# SC8701_EVM_RE1_0624_M6.net
KiCad netlist of a schematic drawn in Altium Designer
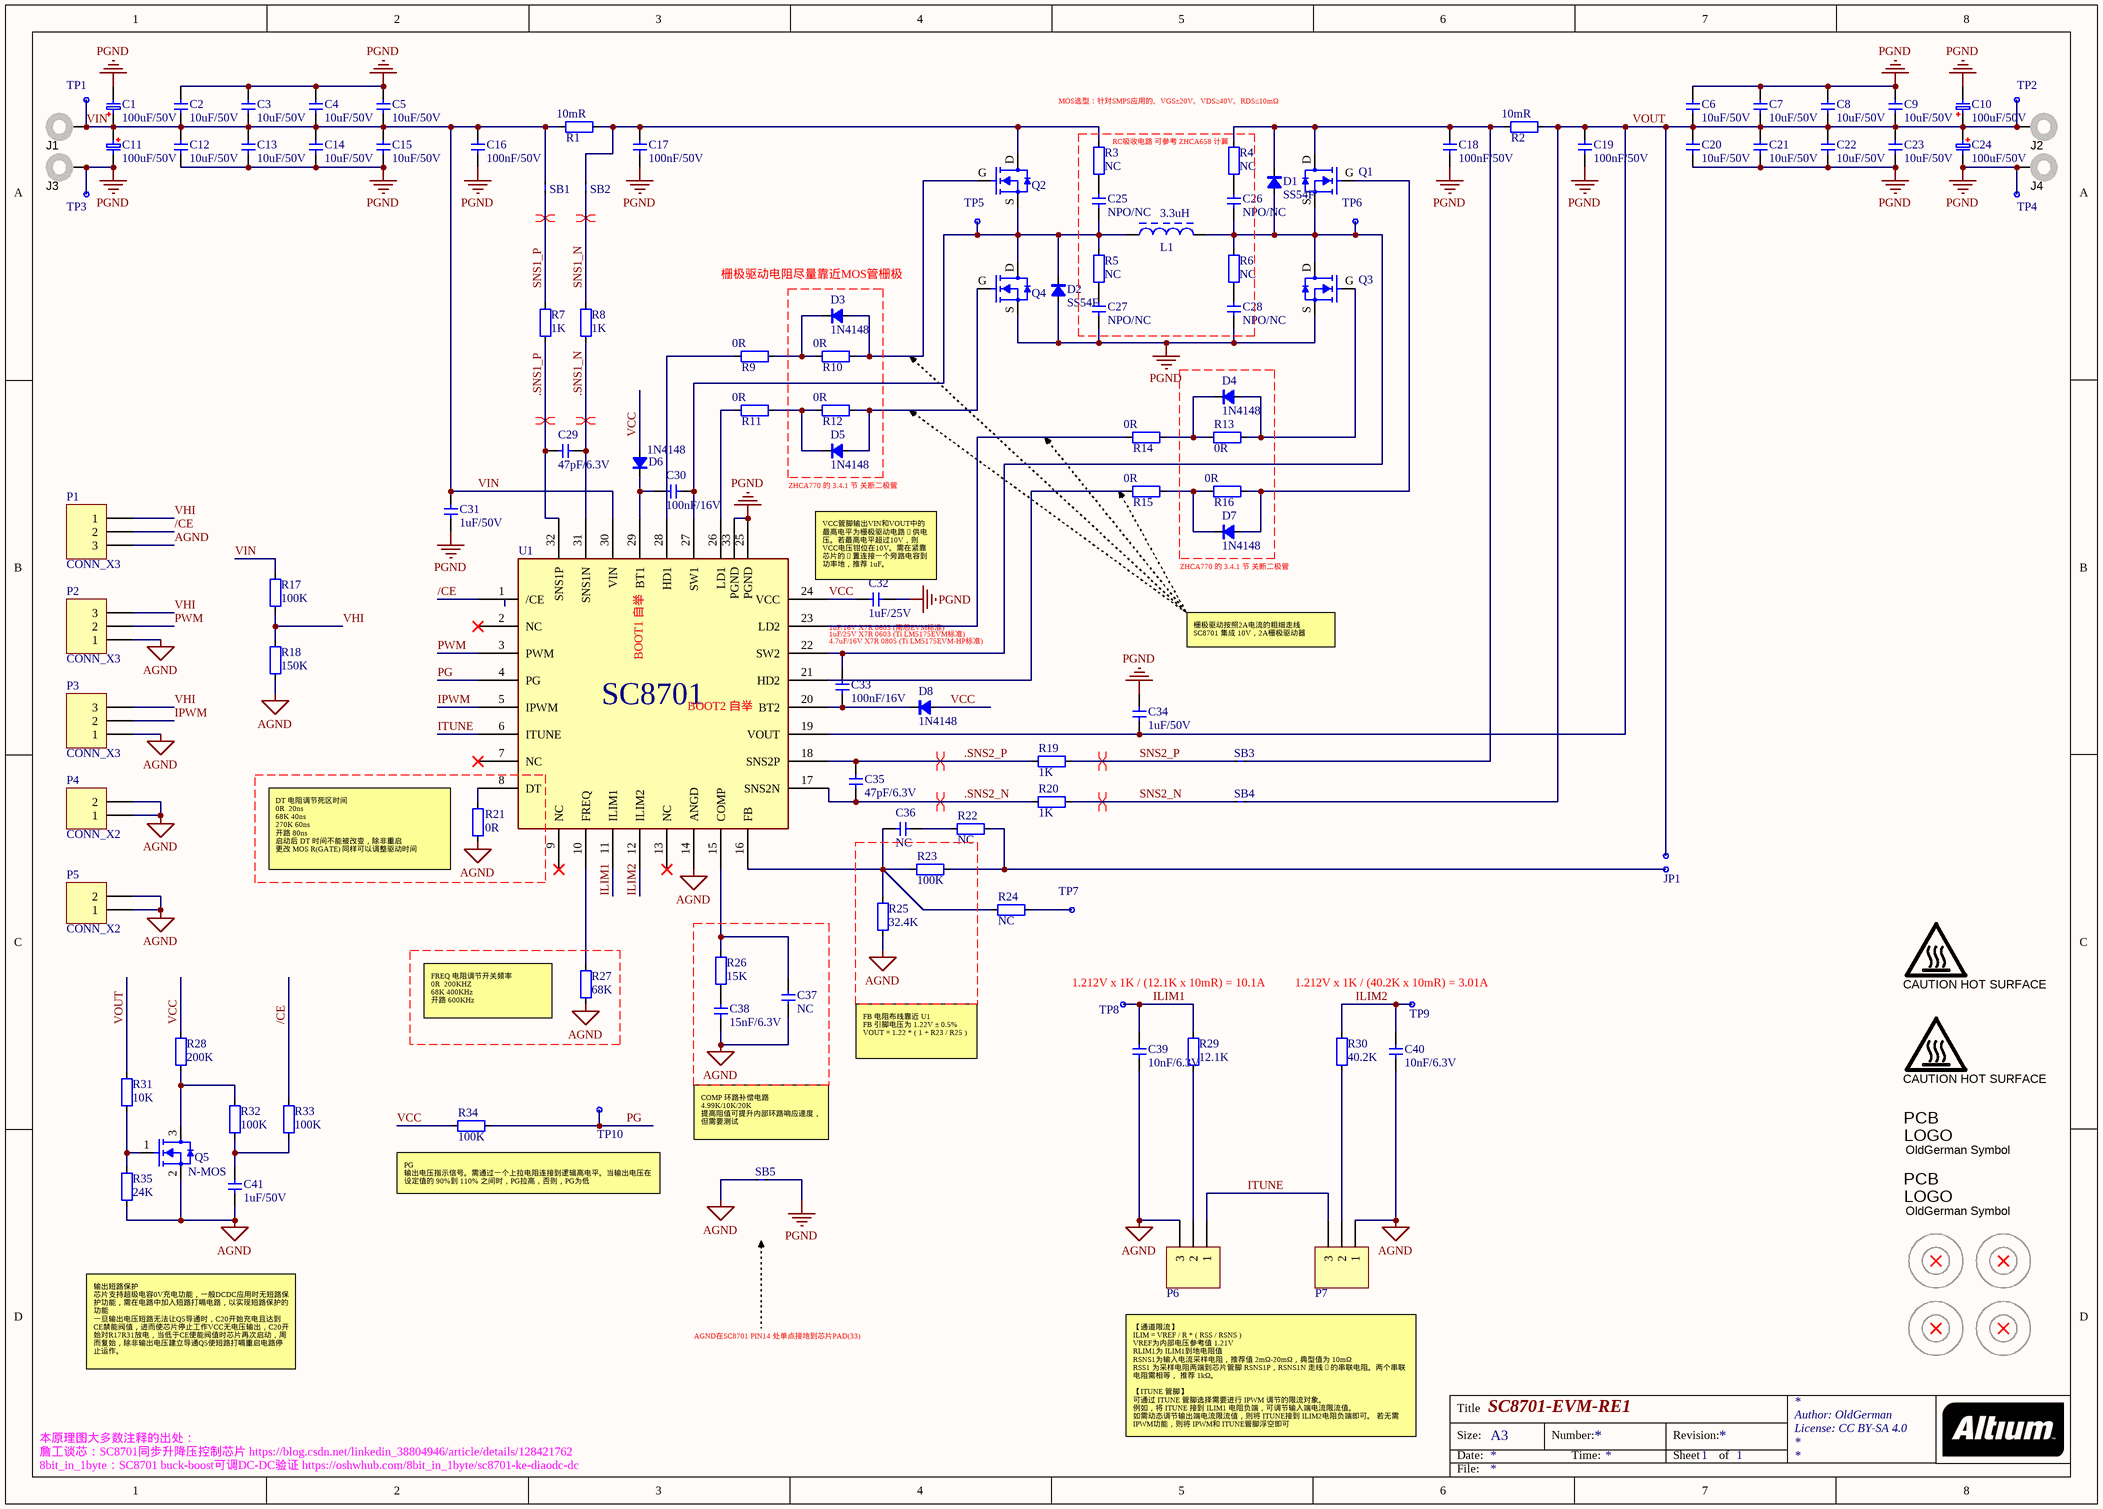
[diagram p0: SC8701_EVM_RE1_0624_M6.SchDoc]

(export (version "E")
  (design (tool "Eeschema 10.0.6"))
  (components
    (comp (ref "C1")
      (value "100uF/50V")
      (footprint "CAP OS-CON D=10.0 L=10.0 F10")
      (description "Capacitor")
      (libsource (lib "ODG_AD_Lib") (part "CAP_Polar_Aluminum"))
    )
    (comp (ref "C2")
      (value "10uF/50V")
      (footprint "C1210")
      (description "Capacitor")
      (libsource (lib "ODG_AD_Lib") (part "CAP"))
    )
    (comp (ref "C3")
      (value "10uF/50V")
      (footprint "C1210")
      (description "Capacitor")
      (libsource (lib "ODG_AD_Lib") (part "CAP"))
    )
    (comp (ref "C4")
      (value "10uF/50V")
      (footprint "C1210")
      (description "Capacitor")
      (libsource (lib "ODG_AD_Lib") (part "CAP"))
    )
    (comp (ref "C5")
      (value "10uF/50V")
      (footprint "C1210")
      (description "Capacitor")
      (libsource (lib "ODG_AD_Lib") (part "CAP"))
    )
    (comp (ref "C6")
      (value "10uF/50V")
      (footprint "C1210")
      (description "Capacitor")
      (libsource (lib "ODG_AD_Lib") (part "CAP"))
    )
    (comp (ref "C7")
      (value "10uF/50V")
      (footprint "C1210")
      (description "Capacitor")
      (libsource (lib "ODG_AD_Lib") (part "CAP"))
    )
    (comp (ref "C8")
      (value "10uF/50V")
      (footprint "C1210")
      (description "Capacitor")
      (libsource (lib "ODG_AD_Lib") (part "CAP"))
    )
    (comp (ref "C9")
      (value "10uF/50V")
      (footprint "C1210")
      (description "Capacitor")
      (libsource (lib "ODG_AD_Lib") (part "CAP"))
    )
    (comp (ref "C10")
      (value "100uF/50V")
      (footprint "CAP OS-CON D=10.0 L=10.0 F10")
      (description "Capacitor")
      (libsource (lib "ODG_AD_Lib") (part "CAP_Polar_Aluminum"))
    )
    (comp (ref "C11")
      (value "100uF/50V")
      (footprint "CAP OS-CON D=10.0 L=10.0 F10")
      (description "Capacitor")
      (libsource (lib "ODG_AD_Lib") (part "CAP_Polar_Aluminum"))
    )
    (comp (ref "C12")
      (value "10uF/50V")
      (footprint "C1210")
      (description "Capacitor")
      (libsource (lib "ODG_AD_Lib") (part "CAP"))
    )
    (comp (ref "C13")
      (value "10uF/50V")
      (footprint "C1210")
      (description "Capacitor")
      (libsource (lib "ODG_AD_Lib") (part "CAP"))
    )
    (comp (ref "C14")
      (value "10uF/50V")
      (footprint "C1210")
      (description "Capacitor")
      (libsource (lib "ODG_AD_Lib") (part "CAP"))
    )
    (comp (ref "C15")
      (value "10uF/50V")
      (footprint "C1210")
      (description "Capacitor")
      (libsource (lib "ODG_AD_Lib") (part "CAP"))
    )
    (comp (ref "C16")
      (value "100nF/50V")
      (footprint "C0603")
      (description "Capacitor")
      (libsource (lib "ODG_AD_Lib") (part "CAP"))
    )
    (comp (ref "C17")
      (value "100nF/50V")
      (footprint "C0603")
      (description "Capacitor")
      (libsource (lib "ODG_AD_Lib") (part "CAP"))
    )
    (comp (ref "C18")
      (value "100nF/50V")
      (footprint "C0603")
      (description "Capacitor")
      (libsource (lib "ODG_AD_Lib") (part "CAP"))
    )
    (comp (ref "C19")
      (value "100nF/50V")
      (footprint "C0603")
      (description "Capacitor")
      (libsource (lib "ODG_AD_Lib") (part "CAP"))
    )
    (comp (ref "C20")
      (value "10uF/50V")
      (footprint "C1210")
      (description "Capacitor")
      (libsource (lib "ODG_AD_Lib") (part "CAP"))
    )
    (comp (ref "C21")
      (value "10uF/50V")
      (footprint "C1210")
      (description "Capacitor")
      (libsource (lib "ODG_AD_Lib") (part "CAP"))
    )
    (comp (ref "C22")
      (value "10uF/50V")
      (footprint "C1210")
      (description "Capacitor")
      (libsource (lib "ODG_AD_Lib") (part "CAP"))
    )
    (comp (ref "C23")
      (value "10uF/50V")
      (footprint "C1210")
      (description "Capacitor")
      (libsource (lib "ODG_AD_Lib") (part "CAP"))
    )
    (comp (ref "C24")
      (value "100uF/50V")
      (footprint "CAP OS-CON D=10.0 L=10.0 F10")
      (description "Capacitor")
      (libsource (lib "ODG_AD_Lib") (part "CAP_Polar_Aluminum"))
    )
    (comp (ref "C25")
      (value "NPO/NC")
      (footprint "C0805")
      (description "Capacitor")
      (libsource (lib "ODG_AD_Lib") (part "CAP"))
    )
    (comp (ref "C26")
      (value "NPO/NC")
      (footprint "C0805")
      (description "Capacitor")
      (libsource (lib "ODG_AD_Lib") (part "CAP"))
    )
    (comp (ref "C27")
      (value "NPO/NC")
      (footprint "C0805")
      (description "Capacitor")
      (libsource (lib "ODG_AD_Lib") (part "CAP"))
    )
    (comp (ref "C28")
      (value "NPO/NC")
      (footprint "C0805")
      (description "Capacitor")
      (libsource (lib "ODG_AD_Lib") (part "CAP"))
    )
    (comp (ref "C29")
      (value "47pF/6.3V")
      (footprint "C0603")
      (description "Capacitor")
      (libsource (lib "ODG_AD_Lib") (part "CAP"))
    )
    (comp (ref "C30")
      (value "100nF/16V")
      (footprint "C0603")
      (description "Capacitor")
      (libsource (lib "ODG_AD_Lib") (part "CAP"))
    )
    (comp (ref "C31")
      (value "1uF/50V")
      (footprint "C0603")
      (description "Capacitor")
      (libsource (lib "ODG_AD_Lib") (part "CAP"))
    )
    (comp (ref "C32")
      (value "1uF/25V")
      (footprint "C0805")
      (description "Capacitor")
      (libsource (lib "ODG_AD_Lib") (part "CAP"))
    )
    (comp (ref "C33")
      (value "100nF/16V")
      (footprint "C0603")
      (description "Capacitor")
      (libsource (lib "ODG_AD_Lib") (part "CAP"))
    )
    (comp (ref "C34")
      (value "1uF/50V")
      (footprint "C0603")
      (description "Capacitor")
      (libsource (lib "ODG_AD_Lib") (part "CAP"))
    )
    (comp (ref "C35")
      (value "47pF/6.3V")
      (footprint "C0603")
      (description "Capacitor")
      (libsource (lib "ODG_AD_Lib") (part "CAP"))
    )
    (comp (ref "C36")
      (value "NC")
      (footprint "C0603")
      (description "Capacitor")
      (libsource (lib "ODG_AD_Lib") (part "CAP"))
    )
    (comp (ref "C37")
      (value "NC")
      (footprint "C0603")
      (description "Capacitor")
      (libsource (lib "ODG_AD_Lib") (part "CAP"))
    )
    (comp (ref "C38")
      (value "15nF/6.3V")
      (footprint "C0603")
      (description "Capacitor")
      (libsource (lib "ODG_AD_Lib") (part "CAP"))
    )
    (comp (ref "C39")
      (value "10nF/6.3V")
      (footprint "C0603")
      (description "Capacitor")
      (libsource (lib "ODG_AD_Lib") (part "CAP"))
    )
    (comp (ref "C40")
      (value "10nF/6.3V")
      (footprint "C0603")
      (description "Capacitor")
      (libsource (lib "ODG_AD_Lib") (part "CAP"))
    )
    (comp (ref "C41")
      (value "1uF/50V")
      (footprint "C0603")
      (description "Capacitor")
      (libsource (lib "ODG_AD_Lib") (part "CAP"))
    )
    (comp (ref "D1")
      (value "SS54F")
      (footprint "SMAF")
      (description "二极管")
      (libsource (lib "") (part "DIODE_2"))
    )
    (comp (ref "D2")
      (value "SS54F")
      (footprint "SMAF")
      (description "二极管")
      (libsource (lib "") (part "DIODE_2"))
    )
    (comp (ref "D3")
      (value "1N4148")
      (footprint "SOD-323")
      (description "二极管")
      (libsource (lib "") (part "DIODE_1"))
    )
    (comp (ref "D4")
      (value "1N4148")
      (footprint "SOD-323")
      (description "二极管")
      (libsource (lib "") (part "DIODE_1"))
    )
    (comp (ref "D5")
      (value "1N4148")
      (footprint "SOD-323")
      (description "二极管")
      (libsource (lib "") (part "DIODE_1"))
    )
    (comp (ref "D6")
      (value "1N4148")
      (footprint "SOD-323")
      (description "二极管")
      (libsource (lib "ODG_AD_Lib") (part "DIODE"))
    )
    (comp (ref "D7")
      (value "1N4148")
      (footprint "SOD-323")
      (description "二极管")
      (libsource (lib "") (part "DIODE_1"))
    )
    (comp (ref "D8")
      (value "1N4148")
      (footprint "SOD-323")
      (description "二极管")
      (libsource (lib "") (part "DIODE_1"))
    )
    (comp (ref "H1") (value "HOLE") (footprint "M3.2 D=8") (libsource (lib "ODG_AD_Lib") (part "HOLE")))
    (comp (ref "H2") (value "HOLE") (footprint "M3.2 D=8") (libsource (lib "ODG_AD_Lib") (part "HOLE")))
    (comp (ref "H3") (value "HOLE") (footprint "M3.2 D=8") (libsource (lib "ODG_AD_Lib") (part "HOLE")))
    (comp (ref "H4") (value "HOLE") (footprint "M3.2 D=8") (libsource (lib "ODG_AD_Lib") (part "HOLE")))
    (comp (ref "J1")
      (value "U6047")
      (footprint "JACK_BANANA_4MM_M6_GE")
      (description "Banana Jack")
      (fields
        (field (name "PARTNUMBER") "575-8")
        (field (name "MANUFACTURER") "Keystone")
        (field (name "PUBLISHER") "Texas Instruments")
      )
      (libsource (lib "ODG_AD_Lib") (part "JACK_BANANA"))
    )
    (comp (ref "J2")
      (value "U6047")
      (footprint "JACK_BANANA_4MM_M6_GE")
      (description "Banana Jack")
      (fields
        (field (name "PARTNUMBER") "575-8")
        (field (name "MANUFACTURER") "Keystone")
        (field (name "PUBLISHER") "Texas Instruments")
      )
      (libsource (lib "ODG_AD_Lib") (part "JACK_BANANA"))
    )
    (comp (ref "J3")
      (value "U6047")
      (footprint "JACK_BANANA_4MM_M6_GE")
      (description "Banana Jack")
      (fields
        (field (name "PARTNUMBER") "575-8")
        (field (name "MANUFACTURER") "Keystone")
        (field (name "PUBLISHER") "Texas Instruments")
      )
      (libsource (lib "ODG_AD_Lib") (part "JACK_BANANA"))
    )
    (comp (ref "J4")
      (value "U6047")
      (footprint "JACK_BANANA_4MM_M6_GE")
      (description "Banana Jack")
      (fields
        (field (name "PARTNUMBER") "575-8")
        (field (name "MANUFACTURER") "Keystone")
        (field (name "PUBLISHER") "Texas Instruments")
      )
      (libsource (lib "ODG_AD_Lib") (part "JACK_BANANA"))
    )
    (comp (ref "JP1")
      (value "CONN_X2_DOT")
      (footprint "2.54mm_Male_x2")
      (libsource (lib "ODG_AD_Lib") (part "CONN_X2_DOT"))
    )
    (comp (ref "L1")
      (value "3.3uH")
      (footprint "INDUCTOR 1350 12.6X13.5X5.0mm")
      (description "135 功率电感 额定电流15A")
      (libsource (lib "ODG_AD_Lib") (part "Inductor_power"))
    )
    (comp (ref "LOGO1")
      (value "CAUTION HOT SURFACE")
      (footprint "IEC_HotSurface_Small")
      (description "IEC 61010-1 Hot Surface Warning")
      (fields (field (name "SYMBOLCREATOR") "a0412235") (field (name "PUBLISHER") "Texas Instruments"))
      (libsource (lib "ODG_AD_Lib") (part "IEC_HotSurface"))
    )
    (comp (ref "LOGO2")
      (value "CAUTION HOT SURFACE")
      (footprint "IEC_HotSurface_Small")
      (description "IEC 61010-1 Hot Surface Warning")
      (fields (field (name "SYMBOLCREATOR") "a0412235") (field (name "PUBLISHER") "Texas Instruments"))
      (libsource (lib "ODG_AD_Lib") (part "IEC_HotSurface"))
    )
    (comp (ref "Logo3")
      (value "OldGerman Symbol")
      (footprint "ODG_LOGO")
      (fields (field (name "SYMBOLCREATOR") "a0412235") (field (name "PUBLISHER") "Texas Instruments"))
      (libsource (lib "ODG_AD_Lib") (part "OldGeman"))
    )
    (comp (ref "Logo4")
      (value "OldGerman Symbol")
      (footprint "ODG_LOGO")
      (fields (field (name "SYMBOLCREATOR") "a0412235") (field (name "PUBLISHER") "Texas Instruments"))
      (libsource (lib "ODG_AD_Lib") (part "OldGeman"))
    )
    (comp (ref "P1") (value "CONN_X3") (footprint "2.54mm_Male_x3") (libsource (lib "") (part "CONN_X3_1")))
    (comp (ref "P2")
      (value "CONN_X3")
      (footprint "2.54mm_Male_x3")
      (libsource (lib "ODG_AD_Lib") (part "CONN_X3"))
    )
    (comp (ref "P3")
      (value "CONN_X3")
      (footprint "2.54mm_Male_x3")
      (libsource (lib "ODG_AD_Lib") (part "CONN_X3"))
    )
    (comp (ref "P4")
      (value "CONN_X2")
      (footprint "2.54mm_Male_x2")
      (libsource (lib "ODG_AD_Lib") (part "CONN_X2"))
    )
    (comp (ref "P5")
      (value "CONN_X2")
      (footprint "2.54mm_Male_x2")
      (libsource (lib "ODG_AD_Lib") (part "CONN_X2"))
    )
    (comp (ref "P6") (value "CONN_X3") (footprint "2.54mm_Male_x3") (libsource (lib "") (part "CONN_X3_1")))
    (comp (ref "P7") (value "CONN_X3") (footprint "2.54mm_Male_x3") (libsource (lib "") (part "CONN_X3_1")))
    (comp (ref "Q1")
      (value "N-MOS_GDS")
      (footprint "SO8FL ROUND")
      (libsource (lib "ODG_AD_Lib") (part "N-MOS_GDS"))
    )
    (comp (ref "Q2")
      (value "N-MOS_GDS")
      (footprint "SO8FL ROUND")
      (libsource (lib "ODG_AD_Lib") (part "N-MOS_GDS"))
    )
    (comp (ref "Q3")
      (value "N-MOS_GDS")
      (footprint "SO8FL ROUND")
      (libsource (lib "ODG_AD_Lib") (part "N-MOS_GDS"))
    )
    (comp (ref "Q4")
      (value "N-MOS_GDS")
      (footprint "SO8FL ROUND")
      (libsource (lib "ODG_AD_Lib") (part "N-MOS_GDS"))
    )
    (comp (ref "Q5")
      (value "N-MOS")
      (footprint "INFINEON SOT-23-3")
      (libsource (lib "ODG_AD_Lib") (part "N-MOS_123"))
    )
    (comp (ref "R1")
      (value "10mR")
      (footprint "R1206")
      (description "IEC Standard")
      (libsource (lib "ODG_AD_Lib") (part "RES"))
    )
    (comp (ref "R2")
      (value "10mR")
      (footprint "R1206")
      (description "IEC Standard")
      (libsource (lib "ODG_AD_Lib") (part "RES"))
    )
    (comp (ref "R3")
      (value "NC")
      (footprint "R0805")
      (description "IEC Standard")
      (libsource (lib "") (part "RES_1"))
    )
    (comp (ref "R4")
      (value "NC")
      (footprint "R0805")
      (description "IEC Standard")
      (libsource (lib "") (part "RES_1"))
    )
    (comp (ref "R5")
      (value "NC")
      (footprint "R0805")
      (description "IEC Standard")
      (libsource (lib "") (part "RES_1"))
    )
    (comp (ref "R6")
      (value "NC")
      (footprint "R0805")
      (description "IEC Standard")
      (libsource (lib "") (part "RES_1"))
    )
    (comp (ref "R7")
      (value "1K")
      (footprint "R0603")
      (description "IEC Standard")
      (libsource (lib "") (part "RES_1"))
    )
    (comp (ref "R8")
      (value "1K")
      (footprint "R0603")
      (description "IEC Standard")
      (libsource (lib "") (part "RES_1"))
    )
    (comp (ref "R9")
      (value "0R")
      (footprint "R0603")
      (description "IEC Standard")
      (libsource (lib "ODG_AD_Lib") (part "RES"))
    )
    (comp (ref "R10")
      (value "0R")
      (footprint "R0603")
      (description "IEC Standard")
      (libsource (lib "ODG_AD_Lib") (part "RES"))
    )
    (comp (ref "R11")
      (value "0R")
      (footprint "R0603")
      (description "IEC Standard")
      (libsource (lib "ODG_AD_Lib") (part "RES"))
    )
    (comp (ref "R12")
      (value "0R")
      (footprint "R0603")
      (description "IEC Standard")
      (libsource (lib "ODG_AD_Lib") (part "RES"))
    )
    (comp (ref "R13")
      (value "0R")
      (footprint "R0603")
      (description "IEC Standard")
      (libsource (lib "ODG_AD_Lib") (part "RES"))
    )
    (comp (ref "R14")
      (value "0R")
      (footprint "R0603")
      (description "IEC Standard")
      (libsource (lib "ODG_AD_Lib") (part "RES"))
    )
    (comp (ref "R15")
      (value "0R")
      (footprint "R0603")
      (description "IEC Standard")
      (libsource (lib "ODG_AD_Lib") (part "RES"))
    )
    (comp (ref "R16")
      (value "0R")
      (footprint "R0603")
      (description "IEC Standard")
      (libsource (lib "ODG_AD_Lib") (part "RES"))
    )
    (comp (ref "R17")
      (value "100K")
      (footprint "R0603")
      (description "IEC Standard")
      (libsource (lib "") (part "RES_1"))
    )
    (comp (ref "R18")
      (value "150K")
      (footprint "R0603")
      (description "IEC Standard")
      (libsource (lib "") (part "RES_1"))
    )
    (comp (ref "R19")
      (value "1K")
      (footprint "R0603")
      (description "IEC Standard")
      (libsource (lib "") (part "RES_2"))
    )
    (comp (ref "R20")
      (value "1K")
      (footprint "R0603")
      (description "IEC Standard")
      (libsource (lib "") (part "RES_2"))
    )
    (comp (ref "R21")
      (value "0R")
      (footprint "R0603")
      (description "IEC Standard")
      (libsource (lib "") (part "RES_1"))
    )
    (comp (ref "R22")
      (value "NC")
      (footprint "R0603")
      (description "IEC Standard")
      (libsource (lib "") (part "RES_2"))
    )
    (comp (ref "R23")
      (value "100K")
      (footprint "R0603")
      (description "IEC Standard")
      (libsource (lib "ODG_AD_Lib") (part "RES"))
    )
    (comp (ref "R24")
      (value "NC")
      (footprint "R0603")
      (description "IEC Standard")
      (libsource (lib "") (part "RES_2"))
    )
    (comp (ref "R25")
      (value "32.4K")
      (footprint "R0603")
      (description "IEC Standard")
      (libsource (lib "") (part "RES_1"))
    )
    (comp (ref "R26")
      (value "15K")
      (footprint "R0603")
      (description "IEC Standard")
      (libsource (lib "") (part "RES_1"))
    )
    (comp (ref "R27")
      (value "68K")
      (footprint "R0603")
      (description "IEC Standard")
      (libsource (lib "") (part "RES_1"))
    )
    (comp (ref "R28")
      (value "200K")
      (footprint "R0603")
      (description "IEC Standard")
      (libsource (lib "") (part "RES_1"))
    )
    (comp (ref "R29")
      (value "12.1K")
      (footprint "R0603")
      (description "IEC Standard")
      (libsource (lib "") (part "RES_1"))
    )
    (comp (ref "R30")
      (value "40.2K")
      (footprint "R0603")
      (description "IEC Standard")
      (libsource (lib "") (part "RES_1"))
    )
    (comp (ref "R31")
      (value "10K")
      (footprint "R0603")
      (description "IEC Standard")
      (libsource (lib "") (part "RES_1"))
    )
    (comp (ref "R32")
      (value "100K")
      (footprint "R0603")
      (description "IEC Standard")
      (libsource (lib "") (part "RES_1"))
    )
    (comp (ref "R33")
      (value "100K")
      (footprint "R0603")
      (description "IEC Standard")
      (libsource (lib "") (part "RES_1"))
    )
    (comp (ref "R34")
      (value "100K")
      (footprint "R0603")
      (description "IEC Standard")
      (libsource (lib "ODG_AD_Lib") (part "RES"))
    )
    (comp (ref "R35")
      (value "24K")
      (footprint "R0603")
      (description "IEC Standard")
      (libsource (lib "") (part "RES_1"))
    )
    (comp (ref "SB1")
      (value "NetTie_200um")
      (footprint "NetTie_200um")
      (description "Net Tie")
      (fields (field (name "PART NUMBER") "NetTie 0.2mm") (field (name "PUBLISHER") "Nordic Semiconductor"))
      (libsource (lib "pca63100") (part "NetTie 0.2mm"))
    )
    (comp (ref "SB2")
      (value "NetTie_200um")
      (footprint "NetTie_200um")
      (description "Net Tie")
      (fields (field (name "PART NUMBER") "NetTie 0.2mm") (field (name "PUBLISHER") "Nordic Semiconductor"))
      (libsource (lib "pca63100") (part "NetTie 0.2mm"))
    )
    (comp (ref "SB3")
      (value "NetTie_200um")
      (footprint "NetTie_200um")
      (description "Net Tie")
      (fields (field (name "PART NUMBER") "NetTie 0.2mm") (field (name "PUBLISHER") "Nordic Semiconductor"))
      (libsource (lib "pca63100") (part "NetTie 0.2mm"))
    )
    (comp (ref "SB4")
      (value "NetTie_200um")
      (footprint "NetTie_200um")
      (description "Net Tie")
      (fields (field (name "PART NUMBER") "NetTie 0.2mm") (field (name "PUBLISHER") "Nordic Semiconductor"))
      (libsource (lib "pca63100") (part "NetTie 0.2mm"))
    )
    (comp (ref "SB5")
      (value "NetTie_200um")
      (footprint "NetTie_200um")
      (description "Net Tie")
      (fields (field (name "PART NUMBER") "NetTie 0.2mm") (field (name "PUBLISHER") "Nordic Semiconductor"))
      (libsource (lib "pca63100") (part "NetTie 0.2mm"))
    )
    (comp (ref "TP1")
      (value "CONN_X1_DOT")
      (footprint "2.54mm_Male_x1")
      (libsource (lib "ODG_AD_Lib") (part "CONN_X1_DOT"))
    )
    (comp (ref "TP2")
      (value "CONN_X1_DOT")
      (footprint "2.54mm_Male_x1")
      (libsource (lib "ODG_AD_Lib") (part "CONN_X1_DOT"))
    )
    (comp (ref "TP3")
      (value "CONN_X1_DOT")
      (footprint "2.54mm_Male_x1")
      (libsource (lib "ODG_AD_Lib") (part "CONN_X1_DOT"))
    )
    (comp (ref "TP4")
      (value "CONN_X1_DOT")
      (footprint "2.54mm_Male_x1")
      (libsource (lib "ODG_AD_Lib") (part "CONN_X1_DOT"))
    )
    (comp (ref "TP5")
      (value "CONN_X1_DOT")
      (footprint "2.54mm_Male_x1")
      (libsource (lib "ODG_AD_Lib") (part "CONN_X1_DOT"))
    )
    (comp (ref "TP6")
      (value "CONN_X1_DOT")
      (footprint "2.54mm_Male_x1")
      (libsource (lib "ODG_AD_Lib") (part "CONN_X1_DOT"))
    )
    (comp (ref "TP7")
      (value "CONN_X1_DOT")
      (footprint "2.54mm_Male_x1")
      (libsource (lib "ODG_AD_Lib") (part "CONN_X1_DOT"))
    )
    (comp (ref "TP8")
      (value "CONN_X1_DOT")
      (footprint "2.54mm_Male_x1")
      (libsource (lib "ODG_AD_Lib") (part "CONN_X1_DOT"))
    )
    (comp (ref "TP9")
      (value "CONN_X1_DOT")
      (footprint "2.54mm_Male_x1")
      (libsource (lib "ODG_AD_Lib") (part "CONN_X1_DOT"))
    )
    (comp (ref "TP10")
      (value "CONN_X1_DOT")
      (footprint "2.54mm_Male_x1")
      (libsource (lib "ODG_AD_Lib") (part "CONN_X1_DOT"))
    )
    (comp (ref "U1")
      (value "SC8701 (A)")
      (footprint "TQFN-32 4X4MM 0.4 VIA")
      (description "高效率, 同步, 4 管升降压控制器")
      (libsource (lib "ODG_AD_Lib") (part "SC8701 (A)"))
    )
  )
  (nets
    (net (code "1") (name "/.SNS1_N") (class "Default")
      (node (ref "C29") (pin "2") (pinfunction "2_2") (pintype "passive"))
      (node (ref "R8") (pin "1") (pinfunction "1_1") (pintype "passive"))
      (node (ref "U1") (pin "31") (pinfunction "SNS1N_31") (pintype "passive"))
    )
    (net (code "2") (name "/.SNS1_P") (class "Default")
      (node (ref "C29") (pin "1") (pinfunction "1_1") (pintype "passive"))
      (node (ref "R7") (pin "1") (pinfunction "1_1") (pintype "passive"))
      (node (ref "U1") (pin "32") (pinfunction "SNS1P_32") (pintype "passive"))
    )
    (net (code "3") (name "/.SNS2_N") (class "Default")
      (node (ref "C35") (pin "2") (pinfunction "2_2") (pintype "passive"))
      (node (ref "R20") (pin "2") (pinfunction "2_2") (pintype "passive"))
      (node (ref "U1") (pin "17") (pinfunction "SNS2N_17") (pintype "passive"))
    )
    (net (code "4") (name "/.SNS2_P") (class "Default")
      (node (ref "C35") (pin "1") (pinfunction "1_1") (pintype "passive"))
      (node (ref "R19") (pin "2") (pinfunction "2_2") (pintype "passive"))
      (node (ref "U1") (pin "18") (pinfunction "SNS2P_18") (pintype "passive"))
    )
    (net (code "5") (name "/ILIM1") (class "Default")
      (node (ref "C39") (pin "2") (pinfunction "2_2") (pintype "passive"))
      (node (ref "R29") (pin "2") (pinfunction "2_2") (pintype "passive"))
      (node (ref "TP8") (pin "1") (pinfunction "1_1") (pintype "passive"))
      (node (ref "U1") (pin "11") (pinfunction "ILIM1_11") (pintype "passive"))
    )
    (net (code "6") (name "/ILIM2") (class "Default")
      (node (ref "C40") (pin "2") (pinfunction "2_2") (pintype "passive"))
      (node (ref "R30") (pin "2") (pinfunction "2_2") (pintype "passive"))
      (node (ref "TP9") (pin "1") (pinfunction "1_1") (pintype "passive"))
      (node (ref "U1") (pin "12") (pinfunction "ILIM2_12") (pintype "passive"))
    )
    (net (code "7") (name "/IPWM") (class "Default")
      (node (ref "P3") (pin "2") (pinfunction "2_2") (pintype "passive"))
      (node (ref "U1") (pin "5") (pinfunction "IPWM_5") (pintype "passive"))
    )
    (net (code "8") (name "/ITUNE") (class "Default")
      (node (ref "P6") (pin "1") (pinfunction "1_1") (pintype "passive"))
      (node (ref "P7") (pin "3") (pinfunction "3_3") (pintype "passive"))
      (node (ref "U1") (pin "6") (pinfunction "ITUNE_6") (pintype "passive"))
    )
    (net (code "9") (name "/PG") (class "Default")
      (node (ref "R34") (pin "2") (pinfunction "2_2") (pintype "passive"))
      (node (ref "TP10") (pin "1") (pinfunction "1_1") (pintype "passive"))
      (node (ref "U1") (pin "4") (pinfunction "PG_4") (pintype "passive"))
    )
    (net (code "10") (name "/PWM") (class "Default")
      (node (ref "P2") (pin "2") (pinfunction "2_2") (pintype "passive"))
      (node (ref "U1") (pin "3") (pinfunction "PWM_3") (pintype "passive"))
    )
    (net (code "11") (name "/SNS1_N") (class "Default")
      (node (ref "R8") (pin "2") (pinfunction "2_2") (pintype "passive"))
      (node (ref "SB2") (pin "1") (pinfunction "1_1") (pintype "passive"))
    )
    (net (code "12") (name "/SNS1_P") (class "Default")
      (node (ref "R7") (pin "2") (pinfunction "2_2") (pintype "passive"))
      (node (ref "SB1") (pin "1") (pinfunction "1_1") (pintype "passive"))
    )
    (net (code "13") (name "/SNS2_N") (class "Default")
      (node (ref "R20") (pin "1") (pinfunction "1_1") (pintype "passive"))
      (node (ref "SB4") (pin "1") (pinfunction "1_1") (pintype "passive"))
    )
    (net (code "14") (name "/SNS2_P") (class "Default")
      (node (ref "R19") (pin "1") (pinfunction "1_1") (pintype "passive"))
      (node (ref "SB3") (pin "1") (pinfunction "1_1") (pintype "passive"))
    )
    (net (code "15") (name "/VCC") (class "Default")
      (node (ref "C32") (pin "1") (pinfunction "1_1") (pintype "passive"))
      (node (ref "D6") (pin "1") (pinfunction "A_1") (pintype "passive"))
      (node (ref "D8") (pin "1") (pinfunction "A_1") (pintype "passive"))
      (node (ref "R28") (pin "2") (pinfunction "2_2") (pintype "passive"))
      (node (ref "R34") (pin "1") (pinfunction "1_1") (pintype "passive"))
      (node (ref "U1") (pin "24") (pinfunction "VCC_24") (pintype "passive"))
    )
    (net (code "16") (name "/VHI") (class "Default")
      (node (ref "P1") (pin "1") (pinfunction "1_1") (pintype "passive"))
      (node (ref "P2") (pin "3") (pinfunction "3_3") (pintype "passive"))
      (node (ref "P3") (pin "3") (pinfunction "3_3") (pintype "passive"))
      (node (ref "R17") (pin "1") (pinfunction "1_1") (pintype "passive"))
      (node (ref "R18") (pin "2") (pinfunction "2_2") (pintype "passive"))
    )
    (net (code "17") (name "/VIN") (class "Default")
      (node (ref "C1") (pin "1") (pinfunction "1_1") (pintype "passive"))
      (node (ref "C11") (pin "1") (pinfunction "1_1") (pintype "passive"))
      (node (ref "C12") (pin "2") (pinfunction "2_2") (pintype "passive"))
      (node (ref "C13") (pin "2") (pinfunction "2_2") (pintype "passive"))
      (node (ref "C14") (pin "2") (pinfunction "2_2") (pintype "passive"))
      (node (ref "C15") (pin "2") (pinfunction "2_2") (pintype "passive"))
      (node (ref "C16") (pin "2") (pinfunction "2_2") (pintype "passive"))
      (node (ref "C2") (pin "2") (pinfunction "2_2") (pintype "passive"))
      (node (ref "C3") (pin "2") (pinfunction "2_2") (pintype "passive"))
      (node (ref "C31") (pin "1") (pinfunction "1_1") (pintype "passive"))
      (node (ref "C4") (pin "2") (pinfunction "2_2") (pintype "passive"))
      (node (ref "C5") (pin "2") (pinfunction "2_2") (pintype "passive"))
      (node (ref "J1") (pin "1") (pinfunction "1_1") (pintype "passive"))
      (node (ref "R1") (pin "1") (pinfunction "1_1") (pintype "passive"))
      (node (ref "R17") (pin "2") (pinfunction "2_2") (pintype "passive"))
      (node (ref "SB1") (pin "2") (pinfunction "2_2") (pintype "passive"))
      (node (ref "TP1") (pin "1") (pinfunction "1_1") (pintype "passive"))
      (node (ref "U1") (pin "30") (pinfunction "VIN_30") (pintype "passive"))
    )
    (net (code "18") (name "/VOUT") (class "Default")
      (node (ref "C10") (pin "1") (pinfunction "1_1") (pintype "passive"))
      (node (ref "C19") (pin "2") (pinfunction "2_2") (pintype "passive"))
      (node (ref "C20") (pin "2") (pinfunction "2_2") (pintype "passive"))
      (node (ref "C21") (pin "2") (pinfunction "2_2") (pintype "passive"))
      (node (ref "C22") (pin "2") (pinfunction "2_2") (pintype "passive"))
      (node (ref "C23") (pin "2") (pinfunction "2_2") (pintype "passive"))
      (node (ref "C24") (pin "1") (pinfunction "1_1") (pintype "passive"))
      (node (ref "C34") (pin "1") (pinfunction "1_1") (pintype "passive"))
      (node (ref "C6") (pin "2") (pinfunction "2_2") (pintype "passive"))
      (node (ref "C7") (pin "2") (pinfunction "2_2") (pintype "passive"))
      (node (ref "C8") (pin "2") (pinfunction "2_2") (pintype "passive"))
      (node (ref "C9") (pin "2") (pinfunction "2_2") (pintype "passive"))
      (node (ref "J2") (pin "1") (pinfunction "1_1") (pintype "passive"))
      (node (ref "JP1") (pin "1") (pinfunction "1_1") (pintype "passive"))
      (node (ref "R2") (pin "2") (pinfunction "2_2") (pintype "passive"))
      (node (ref "R31") (pin "2") (pinfunction "2_2") (pintype "passive"))
      (node (ref "SB4") (pin "2") (pinfunction "2_2") (pintype "passive"))
      (node (ref "TP2") (pin "1") (pinfunction "1_1") (pintype "passive"))
      (node (ref "U1") (pin "19") (pinfunction "VOUT_19") (pintype "passive"))
    )
    (net (code "19") (name "/{slash}CE") (class "Default")
      (node (ref "P1") (pin "2") (pinfunction "2_2") (pintype "passive"))
      (node (ref "R33") (pin "2") (pinfunction "2_2") (pintype "passive"))
      (node (ref "U1") (pin "1") (pinfunction "/CE_1") (pintype "passive"))
    )
    (net (code "20") (name "AGND") (class "Default")
      (node (ref "C37") (pin "1") (pinfunction "1_1") (pintype "passive"))
      (node (ref "C38") (pin "1") (pinfunction "1_1") (pintype "passive"))
      (node (ref "C39") (pin "1") (pinfunction "1_1") (pintype "passive"))
      (node (ref "C40") (pin "1") (pinfunction "1_1") (pintype "passive"))
      (node (ref "C41") (pin "2") (pinfunction "2_2") (pintype "passive"))
      (node (ref "P1") (pin "3") (pinfunction "3_3") (pintype "passive"))
      (node (ref "P2") (pin "1") (pinfunction "1_1") (pintype "passive"))
      (node (ref "P3") (pin "1") (pinfunction "1_1") (pintype "passive"))
      (node (ref "P4") (pin "1") (pinfunction "1_1") (pintype "passive"))
      (node (ref "P4") (pin "2") (pinfunction "2_2") (pintype "passive"))
      (node (ref "P5") (pin "1") (pinfunction "1_1") (pintype "passive"))
      (node (ref "P5") (pin "2") (pinfunction "2_2") (pintype "passive"))
      (node (ref "P6") (pin "3") (pinfunction "3_3") (pintype "passive"))
      (node (ref "P7") (pin "1") (pinfunction "1_1") (pintype "passive"))
      (node (ref "Q5") (pin "2") (pinfunction "S_2") (pintype "passive"))
      (node (ref "R18") (pin "1") (pinfunction "1_1") (pintype "passive"))
      (node (ref "R21") (pin "1") (pinfunction "1_1") (pintype "passive"))
      (node (ref "R25") (pin "1") (pinfunction "1_1") (pintype "passive"))
      (node (ref "R27") (pin "1") (pinfunction "1_1") (pintype "passive"))
      (node (ref "R35") (pin "1") (pinfunction "1_1") (pintype "passive"))
      (node (ref "SB5") (pin "1") (pinfunction "1_1") (pintype "passive"))
      (node (ref "U1") (pin "14") (pinfunction "ANGD_14") (pintype "passive"))
    )
    (net (code "21") (name "Net-(C17-Pad2)") (class "Default")
      (node (ref "C17") (pin "2") (pinfunction "2_2") (pintype "passive"))
      (node (ref "Q2") (pin "D") (pinfunction "D_D") (pintype "passive"))
      (node (ref "R1") (pin "2") (pinfunction "2_2") (pintype "passive"))
      (node (ref "R3") (pin "2") (pinfunction "2_2") (pintype "passive"))
      (node (ref "SB2") (pin "2") (pinfunction "2_2") (pintype "passive"))
    )
    (net (code "22") (name "Net-(C25-Pad2)") (class "Default")
      (node (ref "C25") (pin "2") (pinfunction "2_2") (pintype "passive"))
      (node (ref "R3") (pin "1") (pinfunction "1_1") (pintype "passive"))
    )
    (net (code "23") (name "Net-(C26-Pad2)") (class "Default")
      (node (ref "C26") (pin "2") (pinfunction "2_2") (pintype "passive"))
      (node (ref "R4") (pin "1") (pinfunction "1_1") (pintype "passive"))
    )
    (net (code "24") (name "Net-(C27-Pad2)") (class "Default")
      (node (ref "C27") (pin "2") (pinfunction "2_2") (pintype "passive"))
      (node (ref "R5") (pin "1") (pinfunction "1_1") (pintype "passive"))
    )
    (net (code "25") (name "Net-(C28-Pad2)") (class "Default")
      (node (ref "C28") (pin "2") (pinfunction "2_2") (pintype "passive"))
      (node (ref "R6") (pin "1") (pinfunction "1_1") (pintype "passive"))
    )
    (net (code "26") (name "Net-(C36-Pad2)") (class "Default")
      (node (ref "C36") (pin "2") (pinfunction "2_2") (pintype "passive"))
      (node (ref "R22") (pin "2") (pinfunction "2_2") (pintype "passive"))
    )
    (net (code "27") (name "Net-(C38-Pad2)") (class "Default")
      (node (ref "C38") (pin "2") (pinfunction "2_2") (pintype "passive"))
      (node (ref "R26") (pin "1") (pinfunction "1_1") (pintype "passive"))
    )
    (net (code "28") (name "Net-(C41-Pad1)") (class "Default")
      (node (ref "C41") (pin "1") (pinfunction "1_1") (pintype "passive"))
      (node (ref "R32") (pin "1") (pinfunction "1_1") (pintype "passive"))
      (node (ref "R33") (pin "1") (pinfunction "1_1") (pintype "passive"))
    )
    (net (code "29") (name "Net-(D1-A)") (class "Default")
      (node (ref "C26") (pin "1") (pinfunction "1_1") (pintype "passive"))
      (node (ref "C33") (pin "1") (pinfunction "1_1") (pintype "passive"))
      (node (ref "D1") (pin "1") (pinfunction "A_1") (pintype "passive"))
      (node (ref "L1") (pin "2") (pinfunction "2_2") (pintype "passive"))
      (node (ref "Q1") (pin "S") (pinfunction "S_S") (pintype "passive"))
      (node (ref "Q3") (pin "D") (pinfunction "D_D") (pintype "passive"))
      (node (ref "R6") (pin "2") (pinfunction "2_2") (pintype "passive"))
      (node (ref "TP6") (pin "1") (pinfunction "1_1") (pintype "passive"))
      (node (ref "U1") (pin "22") (pinfunction "SW2_22") (pintype "passive"))
    )
    (net (code "30") (name "Net-(D1-C)") (class "Default")
      (node (ref "C18") (pin "2") (pinfunction "2_2") (pintype "passive"))
      (node (ref "D1") (pin "2") (pinfunction "C_2") (pintype "passive"))
      (node (ref "Q1") (pin "D") (pinfunction "D_D") (pintype "passive"))
      (node (ref "R2") (pin "1") (pinfunction "1_1") (pintype "passive"))
      (node (ref "R4") (pin "2") (pinfunction "2_2") (pintype "passive"))
      (node (ref "SB3") (pin "2") (pinfunction "2_2") (pintype "passive"))
    )
    (net (code "31") (name "Net-(D2-C)") (class "Default")
      (node (ref "C25") (pin "1") (pinfunction "1_1") (pintype "passive"))
      (node (ref "C30") (pin "2") (pinfunction "2_2") (pintype "passive"))
      (node (ref "D2") (pin "2") (pinfunction "C_2") (pintype "passive"))
      (node (ref "L1") (pin "1") (pintype "passive"))
      (node (ref "Q2") (pin "S") (pinfunction "S_S") (pintype "passive"))
      (node (ref "Q4") (pin "D") (pinfunction "D_D") (pintype "passive"))
      (node (ref "R5") (pin "2") (pinfunction "2_2") (pintype "passive"))
      (node (ref "TP5") (pin "1") (pinfunction "1_1") (pintype "passive"))
      (node (ref "U1") (pin "27") (pinfunction "SW1_27") (pintype "passive"))
    )
    (net (code "32") (name "Net-(D3-A)") (class "Default")
      (node (ref "D3") (pin "1") (pinfunction "A_1") (pintype "passive"))
      (node (ref "Q2") (pin "G") (pinfunction "G_G") (pintype "passive"))
      (node (ref "R10") (pin "2") (pinfunction "2_2") (pintype "passive"))
    )
    (net (code "33") (name "Net-(D3-C)") (class "Default")
      (node (ref "D3") (pin "2") (pinfunction "C_2") (pintype "passive"))
      (node (ref "R10") (pin "1") (pinfunction "1_1") (pintype "passive"))
      (node (ref "R9") (pin "2") (pinfunction "2_2") (pintype "passive"))
    )
    (net (code "34") (name "Net-(D4-A)") (class "Default")
      (node (ref "D4") (pin "1") (pinfunction "A_1") (pintype "passive"))
      (node (ref "Q3") (pin "G") (pinfunction "G_G") (pintype "passive"))
      (node (ref "R13") (pin "2") (pinfunction "2_2") (pintype "passive"))
    )
    (net (code "35") (name "Net-(D4-C)") (class "Default")
      (node (ref "D4") (pin "2") (pinfunction "C_2") (pintype "passive"))
      (node (ref "R13") (pin "1") (pinfunction "1_1") (pintype "passive"))
      (node (ref "R14") (pin "2") (pinfunction "2_2") (pintype "passive"))
    )
    (net (code "36") (name "Net-(D5-A)") (class "Default")
      (node (ref "D5") (pin "1") (pinfunction "A_1") (pintype "passive"))
      (node (ref "Q4") (pin "G") (pinfunction "G_G") (pintype "passive"))
      (node (ref "R12") (pin "2") (pinfunction "2_2") (pintype "passive"))
    )
    (net (code "37") (name "Net-(D5-C)") (class "Default")
      (node (ref "D5") (pin "2") (pinfunction "C_2") (pintype "passive"))
      (node (ref "R11") (pin "2") (pinfunction "2_2") (pintype "passive"))
      (node (ref "R12") (pin "1") (pinfunction "1_1") (pintype "passive"))
    )
    (net (code "38") (name "Net-(D6-C)") (class "Default")
      (node (ref "C30") (pin "1") (pinfunction "1_1") (pintype "passive"))
      (node (ref "D6") (pin "2") (pinfunction "C_2") (pintype "passive"))
      (node (ref "U1") (pin "29") (pinfunction "BT1_29") (pintype "passive"))
    )
    (net (code "39") (name "Net-(D7-A)") (class "Default")
      (node (ref "D7") (pin "1") (pinfunction "A_1") (pintype "passive"))
      (node (ref "Q1") (pin "G") (pinfunction "G_G") (pintype "passive"))
      (node (ref "R16") (pin "2") (pinfunction "2_2") (pintype "passive"))
    )
    (net (code "40") (name "Net-(D7-C)") (class "Default")
      (node (ref "D7") (pin "2") (pinfunction "C_2") (pintype "passive"))
      (node (ref "R15") (pin "2") (pinfunction "2_2") (pintype "passive"))
      (node (ref "R16") (pin "1") (pinfunction "1_1") (pintype "passive"))
    )
    (net (code "41") (name "Net-(D8-C)") (class "Default")
      (node (ref "C33") (pin "2") (pinfunction "2_2") (pintype "passive"))
      (node (ref "D8") (pin "2") (pinfunction "C_2") (pintype "passive"))
      (node (ref "U1") (pin "20") (pinfunction "BT2_20") (pintype "passive"))
    )
    (net (code "42") (name "Net-(JP1-Pad2)") (class "Default")
      (node (ref "JP1") (pin "2") (pinfunction "2_2") (pintype "passive"))
      (node (ref "R22") (pin "1") (pinfunction "1_1") (pintype "passive"))
      (node (ref "R23") (pin "2") (pinfunction "2_2") (pintype "passive"))
    )
    (net (code "43") (name "Net-(P6-Pad2)") (class "Default")
      (node (ref "P6") (pin "2") (pinfunction "2_2") (pintype "passive"))
      (node (ref "R29") (pin "1") (pinfunction "1_1") (pintype "passive"))
    )
    (net (code "44") (name "Net-(P7-Pad2)") (class "Default")
      (node (ref "P7") (pin "2") (pinfunction "2_2") (pintype "passive"))
      (node (ref "R30") (pin "1") (pinfunction "1_1") (pintype "passive"))
    )
    (net (code "45") (name "Net-(Q5-D)") (class "Default")
      (node (ref "Q5") (pin "3") (pinfunction "D_3") (pintype "passive"))
      (node (ref "R28") (pin "1") (pinfunction "1_1") (pintype "passive"))
      (node (ref "R32") (pin "2") (pinfunction "2_2") (pintype "passive"))
    )
    (net (code "46") (name "Net-(Q5-G)") (class "Default")
      (node (ref "Q5") (pin "1") (pinfunction "G_1") (pintype "passive"))
      (node (ref "R31") (pin "1") (pinfunction "1_1") (pintype "passive"))
      (node (ref "R35") (pin "2") (pinfunction "2_2") (pintype "passive"))
    )
    (net (code "47") (name "Net-(R24-Pad1)") (class "Default")
      (node (ref "R24") (pin "1") (pinfunction "1_1") (pintype "passive"))
      (node (ref "TP7") (pin "1") (pinfunction "1_1") (pintype "passive"))
    )
    (net (code "48") (name "Net-(U1-COMP)") (class "Default")
      (node (ref "C37") (pin "2") (pinfunction "2_2") (pintype "passive"))
      (node (ref "R26") (pin "2") (pinfunction "2_2") (pintype "passive"))
      (node (ref "U1") (pin "15") (pinfunction "COMP_15") (pintype "passive"))
    )
    (net (code "49") (name "Net-(U1-DT)") (class "Default")
      (node (ref "R21") (pin "2") (pinfunction "2_2") (pintype "passive"))
      (node (ref "U1") (pin "8") (pinfunction "DT_8") (pintype "passive"))
    )
    (net (code "50") (name "Net-(U1-FB)") (class "Default")
      (node (ref "C36") (pin "1") (pinfunction "1_1") (pintype "passive"))
      (node (ref "R23") (pin "1") (pinfunction "1_1") (pintype "passive"))
      (node (ref "R24") (pin "2") (pinfunction "2_2") (pintype "passive"))
      (node (ref "R25") (pin "2") (pinfunction "2_2") (pintype "passive"))
      (node (ref "U1") (pin "16") (pinfunction "FB_16") (pintype "passive"))
    )
    (net (code "51") (name "Net-(U1-FREQ)") (class "Default")
      (node (ref "R27") (pin "2") (pinfunction "2_2") (pintype "passive"))
      (node (ref "U1") (pin "10") (pinfunction "FREQ_10") (pintype "passive"))
    )
    (net (code "52") (name "Net-(U1-HD1)") (class "Default")
      (node (ref "R9") (pin "1") (pinfunction "1_1") (pintype "passive"))
      (node (ref "U1") (pin "28") (pinfunction "HD1_28") (pintype "passive"))
    )
    (net (code "53") (name "Net-(U1-HD2)") (class "Default")
      (node (ref "R15") (pin "1") (pinfunction "1_1") (pintype "passive"))
      (node (ref "U1") (pin "21") (pinfunction "HD2_21") (pintype "passive"))
    )
    (net (code "54") (name "Net-(U1-LD1)") (class "Default")
      (node (ref "R11") (pin "1") (pinfunction "1_1") (pintype "passive"))
      (node (ref "U1") (pin "26") (pinfunction "LD1_26") (pintype "passive"))
    )
    (net (code "55") (name "Net-(U1-LD2)") (class "Default")
      (node (ref "R14") (pin "1") (pinfunction "1_1") (pintype "passive"))
      (node (ref "U1") (pin "23") (pinfunction "LD2_23") (pintype "passive"))
    )
    (net (code "56") (name "PGND") (class "Default")
      (node (ref "C1") (pin "2") (pinfunction "2_2") (pintype "passive"))
      (node (ref "C10") (pin "2") (pinfunction "2_2") (pintype "passive"))
      (node (ref "C11") (pin "2") (pinfunction "2_2") (pintype "passive"))
      (node (ref "C12") (pin "1") (pinfunction "1_1") (pintype "passive"))
      (node (ref "C13") (pin "1") (pinfunction "1_1") (pintype "passive"))
      (node (ref "C14") (pin "1") (pinfunction "1_1") (pintype "passive"))
      (node (ref "C15") (pin "1") (pinfunction "1_1") (pintype "passive"))
      (node (ref "C16") (pin "1") (pinfunction "1_1") (pintype "passive"))
      (node (ref "C17") (pin "1") (pinfunction "1_1") (pintype "passive"))
      (node (ref "C18") (pin "1") (pinfunction "1_1") (pintype "passive"))
      (node (ref "C19") (pin "1") (pinfunction "1_1") (pintype "passive"))
      (node (ref "C2") (pin "1") (pinfunction "1_1") (pintype "passive"))
      (node (ref "C20") (pin "1") (pinfunction "1_1") (pintype "passive"))
      (node (ref "C21") (pin "1") (pinfunction "1_1") (pintype "passive"))
      (node (ref "C22") (pin "1") (pinfunction "1_1") (pintype "passive"))
      (node (ref "C23") (pin "1") (pinfunction "1_1") (pintype "passive"))
      (node (ref "C24") (pin "2") (pinfunction "2_2") (pintype "passive"))
      (node (ref "C27") (pin "1") (pinfunction "1_1") (pintype "passive"))
      (node (ref "C28") (pin "1") (pinfunction "1_1") (pintype "passive"))
      (node (ref "C3") (pin "1") (pinfunction "1_1") (pintype "passive"))
      (node (ref "C31") (pin "2") (pinfunction "2_2") (pintype "passive"))
      (node (ref "C32") (pin "2") (pinfunction "2_2") (pintype "passive"))
      (node (ref "C34") (pin "2") (pinfunction "2_2") (pintype "passive"))
      (node (ref "C4") (pin "1") (pinfunction "1_1") (pintype "passive"))
      (node (ref "C5") (pin "1") (pinfunction "1_1") (pintype "passive"))
      (node (ref "C6") (pin "1") (pinfunction "1_1") (pintype "passive"))
      (node (ref "C7") (pin "1") (pinfunction "1_1") (pintype "passive"))
      (node (ref "C8") (pin "1") (pinfunction "1_1") (pintype "passive"))
      (node (ref "C9") (pin "1") (pinfunction "1_1") (pintype "passive"))
      (node (ref "D2") (pin "1") (pinfunction "A_1") (pintype "passive"))
      (node (ref "J3") (pin "1") (pinfunction "1_1") (pintype "passive"))
      (node (ref "J4") (pin "1") (pinfunction "1_1") (pintype "passive"))
      (node (ref "Q3") (pin "S") (pinfunction "S_S") (pintype "passive"))
      (node (ref "Q4") (pin "S") (pinfunction "S_S") (pintype "passive"))
      (node (ref "SB5") (pin "2") (pinfunction "2_2") (pintype "passive"))
      (node (ref "TP3") (pin "1") (pinfunction "1_1") (pintype "passive"))
      (node (ref "TP4") (pin "1") (pinfunction "1_1") (pintype "passive"))
      (node (ref "U1") (pin "25") (pinfunction "PGND_25") (pintype "passive"))
      (node (ref "U1") (pin "33") (pinfunction "PGND_33") (pintype "passive"))
    )
    (net (code "57") (name "unconnected-(H1-Pad1)") (class "Default")
      (node (ref "H1") (pin "1") (pinfunction "1_1") (pintype "passive+no_connect"))
    )
    (net (code "58") (name "unconnected-(H2-Pad1)") (class "Default")
      (node (ref "H2") (pin "1") (pinfunction "1_1") (pintype "passive+no_connect"))
    )
    (net (code "59") (name "unconnected-(H3-Pad1)") (class "Default")
      (node (ref "H3") (pin "1") (pinfunction "1_1") (pintype "passive+no_connect"))
    )
    (net (code "60") (name "unconnected-(H4-Pad1)") (class "Default")
      (node (ref "H4") (pin "1") (pinfunction "1_1") (pintype "passive+no_connect"))
    )
    (net (code "61") (name "unconnected-(U1-NC-Pad2)") (class "Default")
      (node (ref "U1") (pin "2") (pinfunction "NC_2") (pintype "passive+no_connect"))
    )
    (net (code "62") (name "unconnected-(U1-NC-Pad7)") (class "Default")
      (node (ref "U1") (pin "7") (pinfunction "NC_7") (pintype "passive+no_connect"))
    )
    (net (code "63") (name "unconnected-(U1-NC-Pad9)") (class "Default")
      (node (ref "U1") (pin "9") (pinfunction "NC_9") (pintype "passive+no_connect"))
    )
    (net (code "64") (name "unconnected-(U1-NC-Pad13)") (class "Default")
      (node (ref "U1") (pin "13") (pinfunction "NC_13") (pintype "passive+no_connect"))
    )
  )
)
